# sel.net
KiCad netlist of a schematic drawn in EAGLE
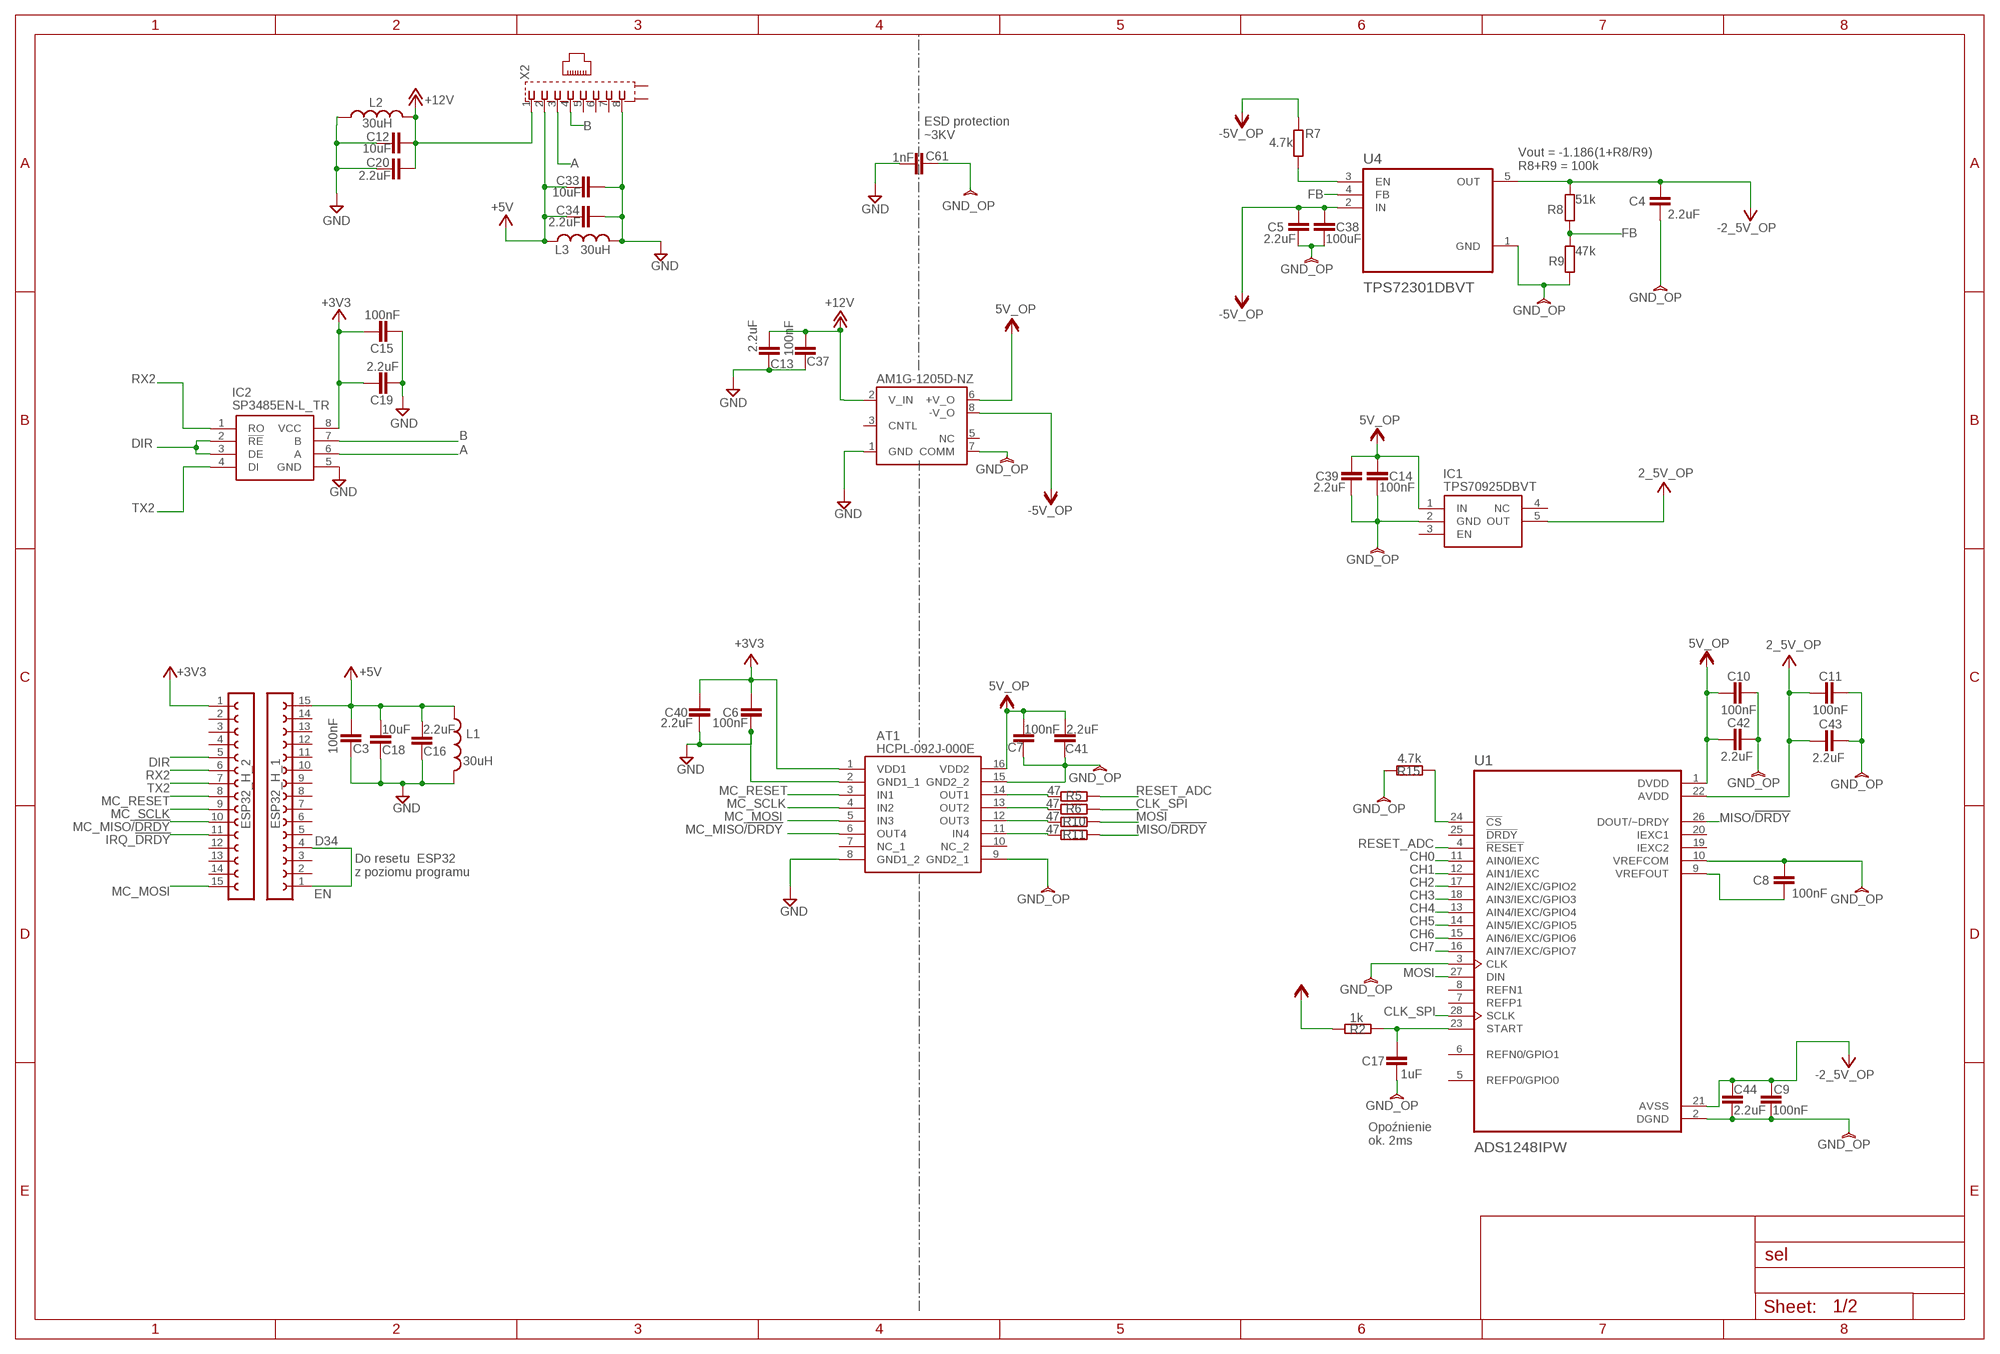
[diagram p0: schematic, sheet 1]
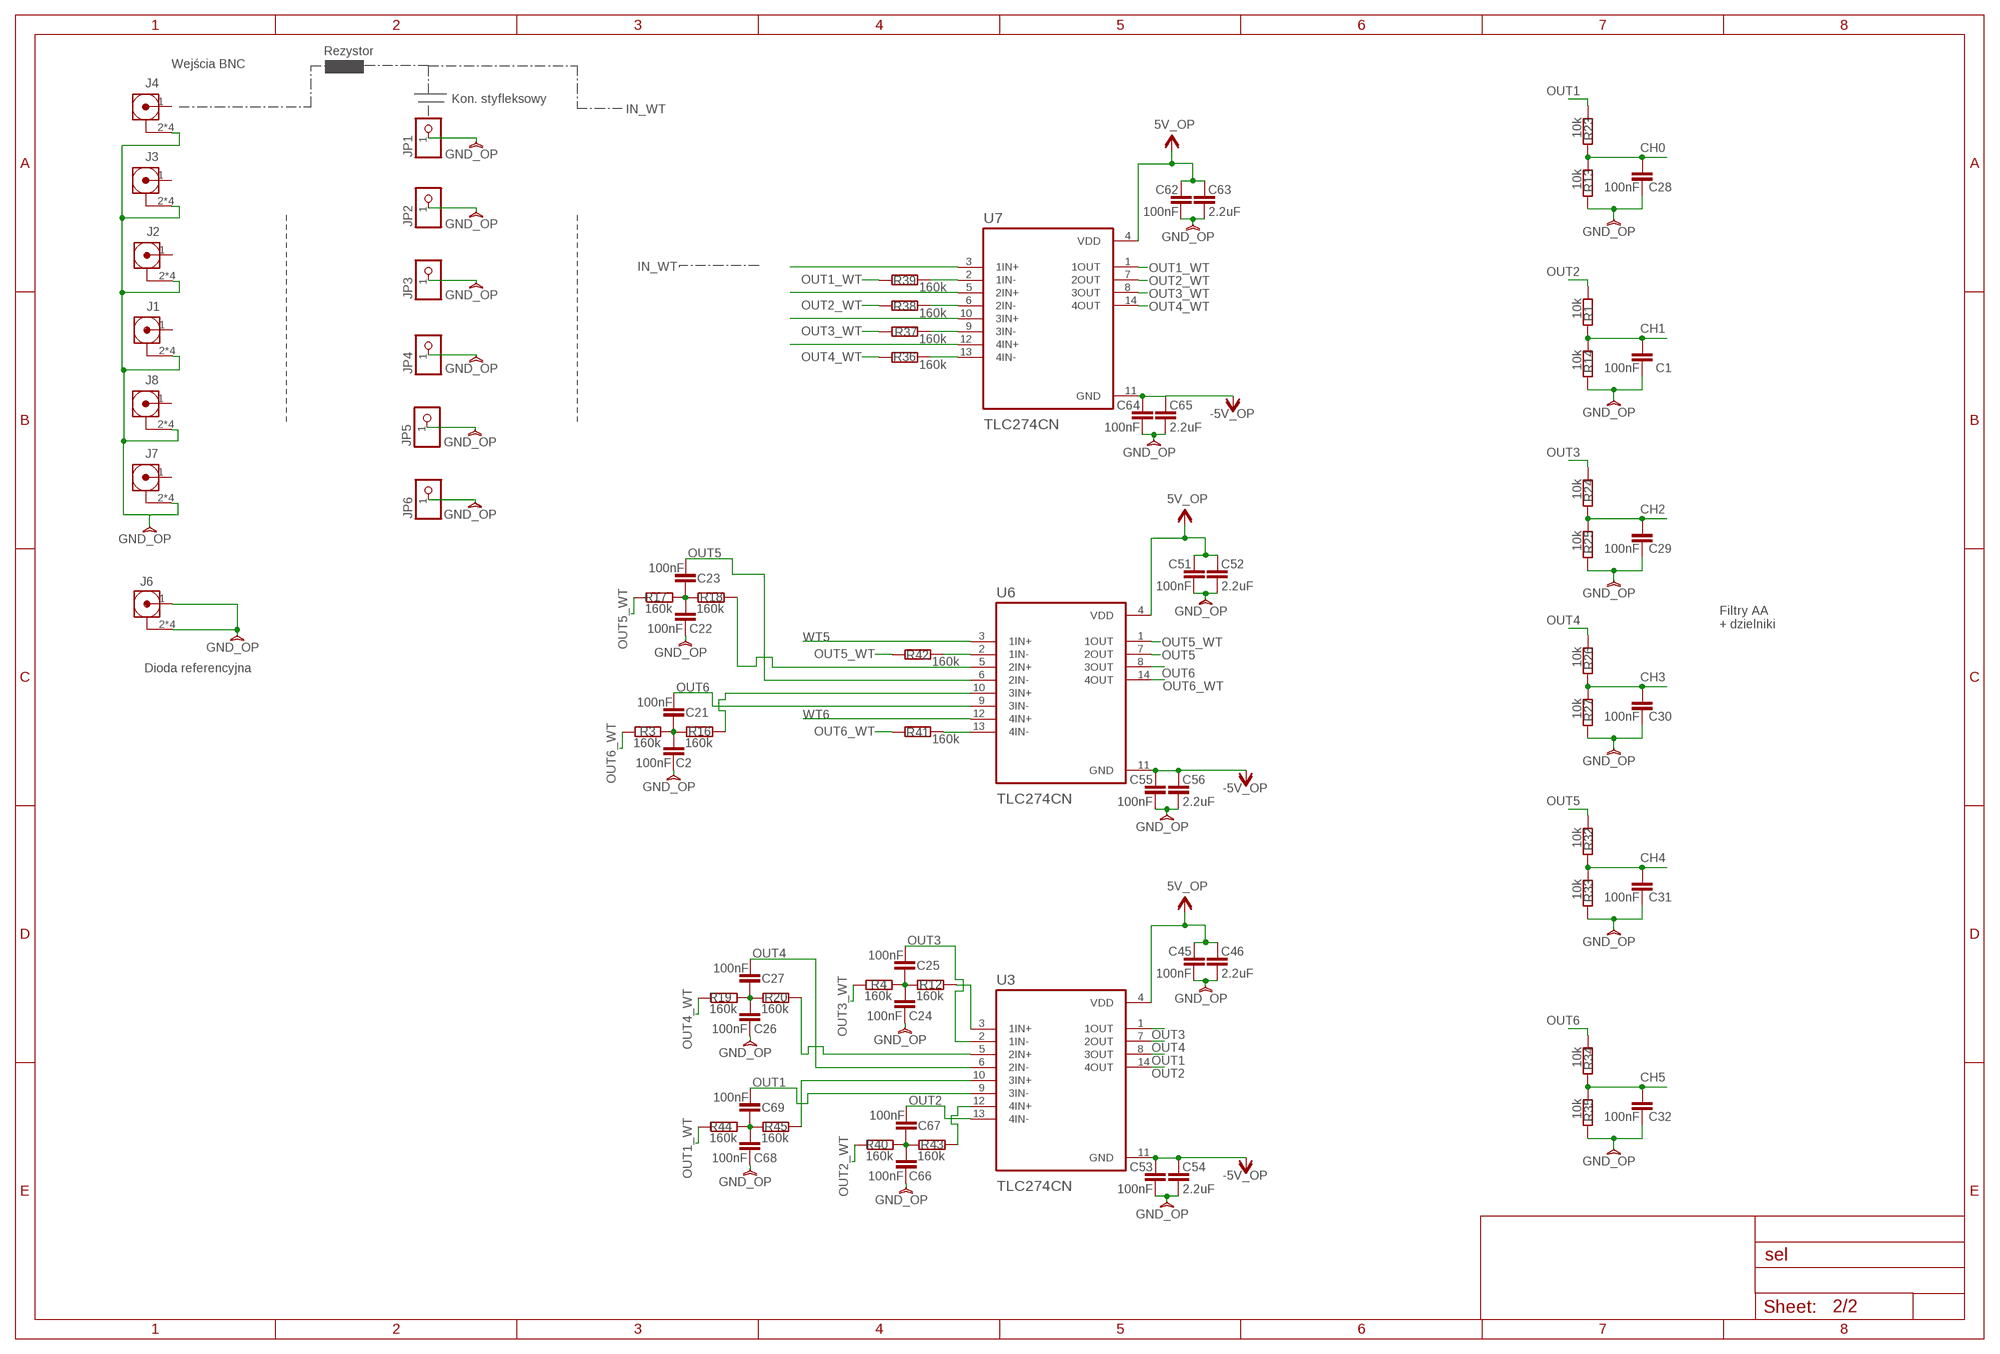
[diagram p1: schematic, sheet 2]

(export (version "E")
  (design (tool "Eeschema 10.0.6"))
  (components
    (comp (ref "AM1G-1205D-NZ")
      (value "AM1G-1205D-NZ")
      (footprint "eagle-import:AM1G-1205D-NZ")
      (libsource (lib "eagle-import") (part "AM1G-1205D-NZ"))
    )
    (comp (ref "AT1")
      (value "HCPL-092J-000E")
      (footprint "eagle-import:SOIC127P600X188-16N")
      (fields (field (name "MOUSER_PART_NUMBER") "630-HCPL-092J-000E"))
      (libsource (lib "eagle-import") (part "HCPL-092J-000E"))
    )
    (comp (ref "C3")
      (value "100nF")
      (footprint "eagle-import:C1206")
      (libsource (lib "eagle-import") (part "C-EUC1206"))
    )
    (comp (ref "C4")
      (value "2.2uF")
      (footprint "eagle-import:C1206")
      (libsource (lib "eagle-import") (part "C-EUC1206"))
    )
    (comp (ref "C5")
      (value "2.2uF")
      (footprint "eagle-import:C1206")
      (libsource (lib "eagle-import") (part "C-EUC1206"))
    )
    (comp (ref "C6")
      (value "100nF")
      (footprint "eagle-import:C1206")
      (libsource (lib "eagle-import") (part "C-EUC1206"))
    )
    (comp (ref "C7")
      (value "100nF")
      (footprint "eagle-import:C1206")
      (libsource (lib "eagle-import") (part "C-EUC1206"))
    )
    (comp (ref "C8")
      (value "100nF")
      (footprint "eagle-import:C1206")
      (libsource (lib "eagle-import") (part "C-EUC1206"))
    )
    (comp (ref "C9")
      (value "100nF")
      (footprint "eagle-import:C1206")
      (libsource (lib "eagle-import") (part "C-EUC1206"))
    )
    (comp (ref "C10")
      (value "100nF")
      (footprint "eagle-import:C1206")
      (libsource (lib "eagle-import") (part "C-EUC1206"))
    )
    (comp (ref "C11")
      (value "100nF")
      (footprint "eagle-import:C1206")
      (libsource (lib "eagle-import") (part "C-EUC1206"))
    )
    (comp (ref "C12")
      (value "10uF")
      (footprint "eagle-import:C1206")
      (libsource (lib "eagle-import") (part "C-EUC1206"))
    )
    (comp (ref "C13")
      (value "2.2uF")
      (footprint "eagle-import:C1206")
      (libsource (lib "eagle-import") (part "C-EUC1206"))
    )
    (comp (ref "C14")
      (value "100nF")
      (footprint "eagle-import:C1206")
      (libsource (lib "eagle-import") (part "C-EUC1206"))
    )
    (comp (ref "C15")
      (value "100nF")
      (footprint "eagle-import:C1206")
      (libsource (lib "eagle-import") (part "C-EUC1206"))
    )
    (comp (ref "C16")
      (value "2.2uF")
      (footprint "eagle-import:C1206")
      (libsource (lib "eagle-import") (part "C-EUC1206"))
    )
    (comp (ref "C17")
      (value "1uF")
      (footprint "eagle-import:C1206")
      (libsource (lib "eagle-import") (part "C-EUC1206"))
    )
    (comp (ref "C18")
      (value "10uF")
      (footprint "eagle-import:C1206")
      (libsource (lib "eagle-import") (part "C-EUC1206"))
    )
    (comp (ref "C19")
      (value "2.2uF")
      (footprint "eagle-import:C1206")
      (libsource (lib "eagle-import") (part "C-EUC1206"))
    )
    (comp (ref "C20")
      (value "2.2uF")
      (footprint "eagle-import:C1206")
      (libsource (lib "eagle-import") (part "C-EUC1206"))
    )
    (comp (ref "C33")
      (value "10uF")
      (footprint "eagle-import:C1206")
      (libsource (lib "eagle-import") (part "C-EUC1206"))
    )
    (comp (ref "C34")
      (value "2.2uF")
      (footprint "eagle-import:C1206")
      (libsource (lib "eagle-import") (part "C-EUC1206"))
    )
    (comp (ref "C37")
      (value "100nF")
      (footprint "eagle-import:C1206")
      (libsource (lib "eagle-import") (part "C-EUC1206"))
    )
    (comp (ref "C38")
      (value "100uF")
      (footprint "eagle-import:C1206")
      (libsource (lib "eagle-import") (part "C-EUC1206"))
    )
    (comp (ref "C39")
      (value "2.2uF")
      (footprint "eagle-import:C1206")
      (libsource (lib "eagle-import") (part "C-EUC1206"))
    )
    (comp (ref "C40")
      (value "2.2uF")
      (footprint "eagle-import:C1206")
      (libsource (lib "eagle-import") (part "C-EUC1206"))
    )
    (comp (ref "C41")
      (value "2.2uF")
      (footprint "eagle-import:C1206")
      (libsource (lib "eagle-import") (part "C-EUC1206"))
    )
    (comp (ref "C42")
      (value "2.2uF")
      (footprint "eagle-import:C1206")
      (libsource (lib "eagle-import") (part "C-EUC1206"))
    )
    (comp (ref "C43")
      (value "2.2uF")
      (footprint "eagle-import:C1206")
      (libsource (lib "eagle-import") (part "C-EUC1206"))
    )
    (comp (ref "C44")
      (value "2.2uF")
      (footprint "eagle-import:C1206")
      (libsource (lib "eagle-import") (part "C-EUC1206"))
    )
    (comp (ref "C61")
      (value "1nF")
      (footprint "eagle-import:C1206")
      (libsource (lib "eagle-import") (part "C-EUC1206"))
    )
    (comp (ref "ESP32_H_1")
      (value "FE15-1")
      (footprint "eagle-import:FE15")
      (libsource (lib "eagle-import") (part "FE15-1"))
    )
    (comp (ref "ESP32_H_2")
      (value "FE15-1")
      (footprint "eagle-import:FE15")
      (libsource (lib "eagle-import") (part "FE15-1"))
    )
    (comp (ref "IC1")
      (value "TPS70925DBVT")
      (footprint "eagle-import:SOT95P280X145-5N")
      (fields (field (name "MOUSER_PART_NUMBER") "595-TPS70925DBVT"))
      (libsource (lib "eagle-import") (part "TPS70925DBVT"))
    )
    (comp (ref "IC2")
      (value "SP3485EN-L_TR")
      (footprint "eagle-import:SOIC127P600X175-8N")
      (fields
        (field (name "MANUFACTURER_PART_NUMBER") "SP3485EN-L/TR")
        (field (name "MOUSER_PART_NUMBER") "701-SP3485EN-L/TR")
      )
      (libsource (lib "eagle-import") (part "SP3485EN-L_TR"))
    )
    (comp (ref "L1")
      (value "30uH")
      (footprint "eagle-import:0204_7")
      (libsource (lib "eagle-import") (part "L-US0204/7"))
    )
    (comp (ref "L2")
      (value "30uH")
      (footprint "eagle-import:0204_7")
      (libsource (lib "eagle-import") (part "L-US0204/7"))
    )
    (comp (ref "L3")
      (value "30uH")
      (footprint "eagle-import:0204_7")
      (libsource (lib "eagle-import") (part "L-US0204/7"))
    )
    (comp (ref "R2")
      (value "1k")
      (footprint "eagle-import:R1206")
      (libsource (lib "eagle-import") (part "R-EU_R1206"))
    )
    (comp (ref "R5")
      (value "47")
      (footprint "eagle-import:R1206")
      (libsource (lib "eagle-import") (part "R-EU_R1206"))
    )
    (comp (ref "R6")
      (value "47")
      (footprint "eagle-import:R1206")
      (libsource (lib "eagle-import") (part "R-EU_R1206"))
    )
    (comp (ref "R7")
      (value "4.7k")
      (footprint "eagle-import:R1206")
      (libsource (lib "eagle-import") (part "R-EU_R1206"))
    )
    (comp (ref "R8")
      (value "51k")
      (footprint "eagle-import:R1206")
      (libsource (lib "eagle-import") (part "R-EU_R1206"))
    )
    (comp (ref "R9")
      (value "47k")
      (footprint "eagle-import:R1206")
      (libsource (lib "eagle-import") (part "R-EU_R1206"))
    )
    (comp (ref "R10")
      (value "47")
      (footprint "eagle-import:R1206")
      (libsource (lib "eagle-import") (part "R-EU_R1206"))
    )
    (comp (ref "R11")
      (value "47")
      (footprint "eagle-import:R1206")
      (libsource (lib "eagle-import") (part "R-EU_R1206"))
    )
    (comp (ref "R15")
      (value "4.7k")
      (footprint "eagle-import:R1206")
      (libsource (lib "eagle-import") (part "R-EU_R1206"))
    )
    (comp (ref "U1")
      (value "ADS1248IPW")
      (footprint "eagle-import:SOP65P640X120-28N")
      (fields (field (name "MF") "Texas Instruments"))
      (libsource (lib "eagle-import") (part "ADS1248IPW"))
    )
    (comp (ref "U4")
      (value "TPS72301DBVT")
      (footprint "eagle-import:SOT95P280X145-5N")
      (fields (field (name "MF") "Texas Instruments"))
      (libsource (lib "eagle-import") (part "TPS72301DBVT"))
    )
    (comp (ref "X2")
      (value "0446200002")
      (footprint "eagle-import:0446200002")
      (fields (field (name "MF") "MOLEX"))
      (libsource (lib "eagle-import") (part "0446200002"))
    )
    (comp (ref "C1")
      (value "100nF")
      (footprint "eagle-import:C1206")
      (libsource (lib "eagle-import") (part "C-EUC1206"))
    )
    (comp (ref "C2")
      (value "100nF")
      (footprint "eagle-import:C1206")
      (libsource (lib "eagle-import") (part "C-EUC1206"))
    )
    (comp (ref "C21")
      (value "100nF")
      (footprint "eagle-import:C1206")
      (libsource (lib "eagle-import") (part "C-EUC1206"))
    )
    (comp (ref "C22")
      (value "100nF")
      (footprint "eagle-import:C1206")
      (libsource (lib "eagle-import") (part "C-EUC1206"))
    )
    (comp (ref "C23")
      (value "100nF")
      (footprint "eagle-import:C1206")
      (libsource (lib "eagle-import") (part "C-EUC1206"))
    )
    (comp (ref "C24")
      (value "100nF")
      (footprint "eagle-import:C1206")
      (libsource (lib "eagle-import") (part "C-EUC1206"))
    )
    (comp (ref "C25")
      (value "100nF")
      (footprint "eagle-import:C1206")
      (libsource (lib "eagle-import") (part "C-EUC1206"))
    )
    (comp (ref "C26")
      (value "100nF")
      (footprint "eagle-import:C1206")
      (libsource (lib "eagle-import") (part "C-EUC1206"))
    )
    (comp (ref "C27")
      (value "100nF")
      (footprint "eagle-import:C1206")
      (libsource (lib "eagle-import") (part "C-EUC1206"))
    )
    (comp (ref "C28")
      (value "100nF")
      (footprint "eagle-import:C1206")
      (libsource (lib "eagle-import") (part "C-EUC1206"))
    )
    (comp (ref "C29")
      (value "100nF")
      (footprint "eagle-import:C1206")
      (libsource (lib "eagle-import") (part "C-EUC1206"))
    )
    (comp (ref "C30")
      (value "100nF")
      (footprint "eagle-import:C1206")
      (libsource (lib "eagle-import") (part "C-EUC1206"))
    )
    (comp (ref "C31")
      (value "100nF")
      (footprint "eagle-import:C1206")
      (libsource (lib "eagle-import") (part "C-EUC1206"))
    )
    (comp (ref "C32")
      (value "100nF")
      (footprint "eagle-import:C1206")
      (libsource (lib "eagle-import") (part "C-EUC1206"))
    )
    (comp (ref "C45")
      (value "100nF")
      (footprint "eagle-import:C1206")
      (libsource (lib "eagle-import") (part "C-EUC1206"))
    )
    (comp (ref "C46")
      (value "2.2uF")
      (footprint "eagle-import:C1206")
      (libsource (lib "eagle-import") (part "C-EUC1206"))
    )
    (comp (ref "C51")
      (value "100nF")
      (footprint "eagle-import:C1206")
      (libsource (lib "eagle-import") (part "C-EUC1206"))
    )
    (comp (ref "C52")
      (value "2.2uF")
      (footprint "eagle-import:C1206")
      (libsource (lib "eagle-import") (part "C-EUC1206"))
    )
    (comp (ref "C53")
      (value "100nF")
      (footprint "eagle-import:C1206")
      (libsource (lib "eagle-import") (part "C-EUC1206"))
    )
    (comp (ref "C54")
      (value "2.2uF")
      (footprint "eagle-import:C1206")
      (libsource (lib "eagle-import") (part "C-EUC1206"))
    )
    (comp (ref "C55")
      (value "100nF")
      (footprint "eagle-import:C1206")
      (libsource (lib "eagle-import") (part "C-EUC1206"))
    )
    (comp (ref "C56")
      (value "2.2uF")
      (footprint "eagle-import:C1206")
      (libsource (lib "eagle-import") (part "C-EUC1206"))
    )
    (comp (ref "C62")
      (value "100nF")
      (footprint "eagle-import:C1206")
      (libsource (lib "eagle-import") (part "C-EUC1206"))
    )
    (comp (ref "C63")
      (value "2.2uF")
      (footprint "eagle-import:C1206")
      (libsource (lib "eagle-import") (part "C-EUC1206"))
    )
    (comp (ref "C64")
      (value "100nF")
      (footprint "eagle-import:C1206")
      (libsource (lib "eagle-import") (part "C-EUC1206"))
    )
    (comp (ref "C65")
      (value "2.2uF")
      (footprint "eagle-import:C1206")
      (libsource (lib "eagle-import") (part "C-EUC1206"))
    )
    (comp (ref "C66")
      (value "100nF")
      (footprint "eagle-import:C1206")
      (libsource (lib "eagle-import") (part "C-EUC1206"))
    )
    (comp (ref "C67")
      (value "100nF")
      (footprint "eagle-import:C1206")
      (libsource (lib "eagle-import") (part "C-EUC1206"))
    )
    (comp (ref "C68")
      (value "100nF")
      (footprint "eagle-import:C1206")
      (libsource (lib "eagle-import") (part "C-EUC1206"))
    )
    (comp (ref "C69")
      (value "100nF")
      (footprint "eagle-import:C1206")
      (libsource (lib "eagle-import") (part "C-EUC1206"))
    )
    (comp (ref "J1")
      (value "5-1634556-0")
      (footprint "eagle-import:TE_5-1634556-0")
      (fields (field (name "MF") "TE Connectivity"))
      (libsource (lib "eagle-import") (part "5-1634556-0"))
    )
    (comp (ref "J2")
      (value "5-1634556-0")
      (footprint "eagle-import:TE_5-1634556-0")
      (fields (field (name "MF") "TE Connectivity"))
      (libsource (lib "eagle-import") (part "5-1634556-0"))
    )
    (comp (ref "J3")
      (value "5-1634556-0")
      (footprint "eagle-import:TE_5-1634556-0")
      (fields (field (name "MF") "TE Connectivity"))
      (libsource (lib "eagle-import") (part "5-1634556-0"))
    )
    (comp (ref "J4")
      (value "5-1634556-0")
      (footprint "eagle-import:TE_5-1634556-0")
      (fields (field (name "MF") "TE Connectivity"))
      (libsource (lib "eagle-import") (part "5-1634556-0"))
    )
    (comp (ref "J6")
      (value "5-1634556-0")
      (footprint "eagle-import:TE_5-1634556-0")
      (fields (field (name "MF") "TE Connectivity"))
      (libsource (lib "eagle-import") (part "5-1634556-0"))
    )
    (comp (ref "J7")
      (value "5-1634556-0")
      (footprint "eagle-import:TE_5-1634556-0")
      (fields (field (name "MF") "TE Connectivity"))
      (libsource (lib "eagle-import") (part "5-1634556-0"))
    )
    (comp (ref "J8")
      (value "5-1634556-0")
      (footprint "eagle-import:TE_5-1634556-0")
      (fields (field (name "MF") "TE Connectivity"))
      (libsource (lib "eagle-import") (part "5-1634556-0"))
    )
    (comp (ref "JP1")
      (value "PINHD-1X1")
      (footprint "eagle-import:1X01")
      (libsource (lib "eagle-import") (part "PINHD-1X1"))
    )
    (comp (ref "JP2")
      (value "PINHD-1X1")
      (footprint "eagle-import:1X01")
      (libsource (lib "eagle-import") (part "PINHD-1X1"))
    )
    (comp (ref "JP3")
      (value "PINHD-1X1")
      (footprint "eagle-import:1X01")
      (libsource (lib "eagle-import") (part "PINHD-1X1"))
    )
    (comp (ref "JP4")
      (value "PINHD-1X1")
      (footprint "eagle-import:1X01")
      (libsource (lib "eagle-import") (part "PINHD-1X1"))
    )
    (comp (ref "JP5")
      (value "PINHD-1X1")
      (footprint "eagle-import:1X01")
      (libsource (lib "eagle-import") (part "PINHD-1X1"))
    )
    (comp (ref "JP6")
      (value "PINHD-1X1")
      (footprint "eagle-import:1X01")
      (libsource (lib "eagle-import") (part "PINHD-1X1"))
    )
    (comp (ref "R1")
      (value "10k")
      (footprint "eagle-import:R1206")
      (libsource (lib "eagle-import") (part "R-EU_R1206"))
    )
    (comp (ref "R3")
      (value "160k")
      (footprint "eagle-import:R1206")
      (libsource (lib "eagle-import") (part "R-EU_R1206"))
    )
    (comp (ref "R4")
      (value "160k")
      (footprint "eagle-import:R1206")
      (libsource (lib "eagle-import") (part "R-EU_R1206"))
    )
    (comp (ref "R12")
      (value "160k")
      (footprint "eagle-import:R1206")
      (libsource (lib "eagle-import") (part "R-EU_R1206"))
    )
    (comp (ref "R13")
      (value "10k")
      (footprint "eagle-import:R1206")
      (libsource (lib "eagle-import") (part "R-EU_R1206"))
    )
    (comp (ref "R14")
      (value "10k")
      (footprint "eagle-import:R1206")
      (libsource (lib "eagle-import") (part "R-EU_R1206"))
    )
    (comp (ref "R16")
      (value "160k")
      (footprint "eagle-import:R1206")
      (libsource (lib "eagle-import") (part "R-EU_R1206"))
    )
    (comp (ref "R17")
      (value "160k")
      (footprint "eagle-import:R1206")
      (libsource (lib "eagle-import") (part "R-EU_R1206"))
    )
    (comp (ref "R18")
      (value "160k")
      (footprint "eagle-import:R1206")
      (libsource (lib "eagle-import") (part "R-EU_R1206"))
    )
    (comp (ref "R19")
      (value "160k")
      (footprint "eagle-import:R1206")
      (libsource (lib "eagle-import") (part "R-EU_R1206"))
    )
    (comp (ref "R20")
      (value "160k")
      (footprint "eagle-import:R1206")
      (libsource (lib "eagle-import") (part "R-EU_R1206"))
    )
    (comp (ref "R23")
      (value "10k")
      (footprint "eagle-import:R1206")
      (libsource (lib "eagle-import") (part "R-EU_R1206"))
    )
    (comp (ref "R24")
      (value "10k")
      (footprint "eagle-import:R1206")
      (libsource (lib "eagle-import") (part "R-EU_R1206"))
    )
    (comp (ref "R25")
      (value "10k")
      (footprint "eagle-import:R1206")
      (libsource (lib "eagle-import") (part "R-EU_R1206"))
    )
    (comp (ref "R26")
      (value "10k")
      (footprint "eagle-import:R1206")
      (libsource (lib "eagle-import") (part "R-EU_R1206"))
    )
    (comp (ref "R27")
      (value "10k")
      (footprint "eagle-import:R1206")
      (libsource (lib "eagle-import") (part "R-EU_R1206"))
    )
    (comp (ref "R32")
      (value "10k")
      (footprint "eagle-import:R1206")
      (libsource (lib "eagle-import") (part "R-EU_R1206"))
    )
    (comp (ref "R33")
      (value "10k")
      (footprint "eagle-import:R1206")
      (libsource (lib "eagle-import") (part "R-EU_R1206"))
    )
    (comp (ref "R34")
      (value "10k")
      (footprint "eagle-import:R1206")
      (libsource (lib "eagle-import") (part "R-EU_R1206"))
    )
    (comp (ref "R35")
      (value "10k")
      (footprint "eagle-import:R1206")
      (libsource (lib "eagle-import") (part "R-EU_R1206"))
    )
    (comp (ref "R36")
      (value "160k")
      (footprint "eagle-import:R1206")
      (libsource (lib "eagle-import") (part "R-EU_R1206"))
    )
    (comp (ref "R37")
      (value "160k")
      (footprint "eagle-import:R1206")
      (libsource (lib "eagle-import") (part "R-EU_R1206"))
    )
    (comp (ref "R38")
      (value "160k")
      (footprint "eagle-import:R1206")
      (libsource (lib "eagle-import") (part "R-EU_R1206"))
    )
    (comp (ref "R39")
      (value "160k")
      (footprint "eagle-import:R1206")
      (libsource (lib "eagle-import") (part "R-EU_R1206"))
    )
    (comp (ref "R40")
      (value "160k")
      (footprint "eagle-import:R1206")
      (libsource (lib "eagle-import") (part "R-EU_R1206"))
    )
    (comp (ref "R41")
      (value "160k")
      (footprint "eagle-import:R1206")
      (libsource (lib "eagle-import") (part "R-EU_R1206"))
    )
    (comp (ref "R42")
      (value "160k")
      (footprint "eagle-import:R1206")
      (libsource (lib "eagle-import") (part "R-EU_R1206"))
    )
    (comp (ref "R43")
      (value "160k")
      (footprint "eagle-import:R1206")
      (libsource (lib "eagle-import") (part "R-EU_R1206"))
    )
    (comp (ref "R44")
      (value "160k")
      (footprint "eagle-import:R1206")
      (libsource (lib "eagle-import") (part "R-EU_R1206"))
    )
    (comp (ref "R45")
      (value "160k")
      (footprint "eagle-import:R1206")
      (libsource (lib "eagle-import") (part "R-EU_R1206"))
    )
    (comp (ref "U3")
      (value "TLC274CN")
      (footprint "eagle-import:DIP794W45P254L1969H508Q14")
      (fields (field (name "MF") "Texas Instruments"))
      (libsource (lib "eagle-import") (part "TLC274CN"))
    )
    (comp (ref "U6")
      (value "TLC274CN")
      (footprint "eagle-import:DIP794W45P254L1969H508Q14")
      (fields (field (name "MF") "Texas Instruments"))
      (libsource (lib "eagle-import") (part "TLC274CN"))
    )
    (comp (ref "U7")
      (value "TLC274CN")
      (footprint "eagle-import:DIP794W45P254L1969H508Q14")
      (fields (field (name "MF") "Texas Instruments"))
      (libsource (lib "eagle-import") (part "TLC274CN"))
    )
  )
  (nets
    (net (code "1") (name "+3V3") (class "Default")
      (node (ref "AT1") (pin "1") (pinfunction "VDD1_1") (pintype "bidirectional"))
      (node (ref "C15") (pin "2") (pinfunction "2_2") (pintype "passive"))
      (node (ref "C19") (pin "2") (pinfunction "2_2") (pintype "passive"))
      (node (ref "C40") (pin "2") (pinfunction "2_2") (pintype "passive"))
      (node (ref "C6") (pin "2") (pinfunction "2_2") (pintype "passive"))
      (node (ref "ESP32_H_2") (pin "1") (pinfunction "1_1") (pintype "passive"))
      (node (ref "IC2") (pin "8") (pinfunction "VCC_8") (pintype "bidirectional"))
    )
    (net (code "2") (name "+5V") (class "Default")
      (node (ref "C16") (pin "1") (pinfunction "1_1") (pintype "passive"))
      (node (ref "C18") (pin "1") (pinfunction "1_1") (pintype "passive"))
      (node (ref "C3") (pin "1") (pinfunction "1_1") (pintype "passive"))
      (node (ref "C33") (pin "2") (pinfunction "2_2") (pintype "passive"))
      (node (ref "C34") (pin "2") (pinfunction "2_2") (pintype "passive"))
      (node (ref "ESP32_H_1") (pin "15") (pinfunction "15_15") (pintype "passive"))
      (node (ref "L1") (pin "1") (pinfunction "1_1") (pintype "passive"))
      (node (ref "L3") (pin "1") (pinfunction "1_1") (pintype "passive"))
      (node (ref "X2") (pin "2") (pinfunction "2_2") (pintype "passive"))
    )
    (net (code "3") (name "+12V") (class "Default")
      (node (ref "AM1G-1205D-NZ") (pin "2") (pinfunction "V_IN_2") (pintype "bidirectional"))
      (node (ref "C12") (pin "1") (pinfunction "1_1") (pintype "passive"))
      (node (ref "C13") (pin "2") (pinfunction "2_2") (pintype "passive"))
      (node (ref "C20") (pin "1") (pinfunction "1_1") (pintype "passive"))
      (node (ref "C37") (pin "2") (pinfunction "2_2") (pintype "passive"))
      (node (ref "L2") (pin "2") (pinfunction "2_2") (pintype "passive"))
      (node (ref "X2") (pin "1") (pinfunction "1_1") (pintype "passive"))
    )
    (net (code "4") (name "-2_5V_OP") (class "Default")
      (node (ref "C4") (pin "1") (pinfunction "1_1") (pintype "passive"))
      (node (ref "C44") (pin "1") (pinfunction "1_1") (pintype "passive"))
      (node (ref "C9") (pin "1") (pinfunction "1_1") (pintype "passive"))
      (node (ref "R8") (pin "2") (pinfunction "2_2") (pintype "passive"))
      (node (ref "U1") (pin "21") (pinfunction "AVSS_21") (pintype "power_in"))
      (node (ref "U4") (pin "5") (pinfunction "OUT_5") (pintype "output"))
    )
    (net (code "5") (name "-5V_OP") (class "Default")
      (node (ref "AM1G-1205D-NZ") (pin "8") (pinfunction "-V_O_8") (pintype "bidirectional"))
      (node (ref "C38") (pin "1") (pinfunction "1_1") (pintype "passive"))
      (node (ref "C5") (pin "1") (pinfunction "1_1") (pintype "passive"))
      (node (ref "C53") (pin "2") (pinfunction "2_2") (pintype "passive"))
      (node (ref "C54") (pin "2") (pinfunction "2_2") (pintype "passive"))
      (node (ref "C55") (pin "2") (pinfunction "2_2") (pintype "passive"))
      (node (ref "C56") (pin "2") (pinfunction "2_2") (pintype "passive"))
      (node (ref "C64") (pin "2") (pinfunction "2_2") (pintype "passive"))
      (node (ref "C65") (pin "2") (pinfunction "2_2") (pintype "passive"))
      (node (ref "R7") (pin "1") (pinfunction "1_1") (pintype "passive"))
      (node (ref "U3") (pin "11") (pinfunction "GND_11") (pintype "power_in"))
      (node (ref "U4") (pin "2") (pinfunction "IN_2") (pintype "input"))
      (node (ref "U6") (pin "11") (pinfunction "GND_11") (pintype "power_in"))
      (node (ref "U7") (pin "11") (pinfunction "GND_11") (pintype "power_in"))
    )
    (net (code "6") (name "2_5V_OP") (class "Default")
      (node (ref "C11") (pin "2") (pinfunction "2_2") (pintype "passive"))
      (node (ref "C43") (pin "2") (pinfunction "2_2") (pintype "passive"))
      (node (ref "IC1") (pin "5") (pinfunction "OUT_5") (pintype "bidirectional"))
      (node (ref "U1") (pin "22") (pinfunction "AVDD_22") (pintype "power_in"))
    )
    (net (code "7") (name "5V_OP") (class "Default")
      (node (ref "AM1G-1205D-NZ") (pin "6") (pinfunction "+V_O_6") (pintype "bidirectional"))
      (node (ref "AT1") (pin "16") (pinfunction "VDD2_16") (pintype "bidirectional"))
      (node (ref "C10") (pin "2") (pinfunction "2_2") (pintype "passive"))
      (node (ref "C14") (pin "1") (pinfunction "1_1") (pintype "passive"))
      (node (ref "C39") (pin "1") (pinfunction "1_1") (pintype "passive"))
      (node (ref "C41") (pin "1") (pinfunction "1_1") (pintype "passive"))
      (node (ref "C42") (pin "2") (pinfunction "2_2") (pintype "passive"))
      (node (ref "C45") (pin "2") (pinfunction "2_2") (pintype "passive"))
      (node (ref "C46") (pin "2") (pinfunction "2_2") (pintype "passive"))
      (node (ref "C51") (pin "2") (pinfunction "2_2") (pintype "passive"))
      (node (ref "C52") (pin "2") (pinfunction "2_2") (pintype "passive"))
      (node (ref "C62") (pin "2") (pinfunction "2_2") (pintype "passive"))
      (node (ref "C63") (pin "2") (pinfunction "2_2") (pintype "passive"))
      (node (ref "C7") (pin "1") (pinfunction "1_1") (pintype "passive"))
      (node (ref "IC1") (pin "1") (pinfunction "IN_1") (pintype "bidirectional"))
      (node (ref "R2") (pin "2") (pinfunction "2_2") (pintype "passive"))
      (node (ref "U1") (pin "1") (pinfunction "DVDD_1") (pintype "power_in"))
      (node (ref "U3") (pin "4") (pinfunction "VDD_4") (pintype "power_in"))
      (node (ref "U6") (pin "4") (pinfunction "VDD_4") (pintype "power_in"))
      (node (ref "U7") (pin "4") (pinfunction "VDD_4") (pintype "power_in"))
    )
    (net (code "8") (name "A") (class "Default")
      (node (ref "IC2") (pin "6") (pinfunction "A_6") (pintype "bidirectional"))
      (node (ref "X2") (pin "3") (pinfunction "3_3") (pintype "passive"))
    )
    (net (code "9") (name "B") (class "Default")
      (node (ref "IC2") (pin "7") (pinfunction "B_7") (pintype "bidirectional"))
      (node (ref "X2") (pin "4") (pinfunction "4_4") (pintype "passive"))
    )
    (net (code "10") (name "CH0") (class "Default")
      (node (ref "C28") (pin "1") (pinfunction "1_1") (pintype "passive"))
      (node (ref "R13") (pin "2") (pinfunction "2_2") (pintype "passive"))
      (node (ref "R23") (pin "1") (pinfunction "1_1") (pintype "passive"))
      (node (ref "U1") (pin "11") (pinfunction "AIN0/IEXC_11") (pintype "input"))
    )
    (net (code "11") (name "CH1") (class "Default")
      (node (ref "C1") (pin "1") (pinfunction "1_1") (pintype "passive"))
      (node (ref "R1") (pin "1") (pinfunction "1_1") (pintype "passive"))
      (node (ref "R14") (pin "2") (pinfunction "2_2") (pintype "passive"))
      (node (ref "U1") (pin "12") (pinfunction "AIN1/IEXC_12") (pintype "input"))
    )
    (net (code "12") (name "CH2") (class "Default")
      (node (ref "C29") (pin "1") (pinfunction "1_1") (pintype "passive"))
      (node (ref "R24") (pin "1") (pinfunction "1_1") (pintype "passive"))
      (node (ref "R25") (pin "2") (pinfunction "2_2") (pintype "passive"))
      (node (ref "U1") (pin "17") (pinfunction "AIN2/IEXC/GPIO2_17") (pintype "input"))
    )
    (net (code "13") (name "CH3") (class "Default")
      (node (ref "C30") (pin "1") (pinfunction "1_1") (pintype "passive"))
      (node (ref "R26") (pin "1") (pinfunction "1_1") (pintype "passive"))
      (node (ref "R27") (pin "2") (pinfunction "2_2") (pintype "passive"))
      (node (ref "U1") (pin "18") (pinfunction "AIN3/IEXC/GPIO3_18") (pintype "input"))
    )
    (net (code "14") (name "CH4") (class "Default")
      (node (ref "C31") (pin "1") (pinfunction "1_1") (pintype "passive"))
      (node (ref "R32") (pin "1") (pinfunction "1_1") (pintype "passive"))
      (node (ref "R33") (pin "2") (pinfunction "2_2") (pintype "passive"))
      (node (ref "U1") (pin "13") (pinfunction "AIN4/IEXC/GPIO4_13") (pintype "input"))
    )
    (net (code "15") (name "CH5") (class "Default")
      (node (ref "C32") (pin "1") (pinfunction "1_1") (pintype "passive"))
      (node (ref "R34") (pin "1") (pinfunction "1_1") (pintype "passive"))
      (node (ref "R35") (pin "2") (pinfunction "2_2") (pintype "passive"))
      (node (ref "U1") (pin "14") (pinfunction "AIN5/IEXC/GPIO5_14") (pintype "input"))
    )
    (net (code "16") (name "CH6") (class "Default")
      (node (ref "U1") (pin "15") (pinfunction "AIN6/IEXC/GPIO6_15") (pintype "input"))
    )
    (net (code "17") (name "CH7") (class "Default")
      (node (ref "U1") (pin "16") (pinfunction "AIN7/IEXC/GPIO7_16") (pintype "input"))
    )
    (net (code "18") (name "CLK_SPI") (class "Default")
      (node (ref "AT1") (pin "13") (pinfunction "OUT2_13") (pintype "bidirectional"))
      (node (ref "R6") (pin "2") (pinfunction "2_2") (pintype "passive"))
      (node (ref "U1") (pin "28") (pinfunction "SCLK_28") (pintype "input"))
    )
    (net (code "19") (name "DIR") (class "Default")
      (node (ref "ESP32_H_2") (pin "5") (pinfunction "5_5") (pintype "passive"))
      (node (ref "IC2") (pin "2") (pinfunction "~{RE}_2") (pintype "bidirectional"))
      (node (ref "IC2") (pin "3") (pinfunction "DE_3") (pintype "bidirectional"))
    )
    (net (code "20") (name "EN") (class "Default")
      (node (ref "ESP32_H_1") (pin "1") (pinfunction "1_1") (pintype "passive"))
      (node (ref "ESP32_H_1") (pin "4") (pinfunction "4_4") (pintype "passive"))
    )
    (net (code "21") (name "FB") (class "Default")
      (node (ref "R8") (pin "1") (pinfunction "1_1") (pintype "passive"))
      (node (ref "R9") (pin "2") (pinfunction "2_2") (pintype "passive"))
      (node (ref "U4") (pin "4") (pinfunction "FB_4") (pintype "input"))
    )
    (net (code "22") (name "GND") (class "Default")
      (node (ref "AM1G-1205D-NZ") (pin "1") (pinfunction "GND_1") (pintype "bidirectional"))
      (node (ref "AT1") (pin "2") (pinfunction "GND1_1_2") (pintype "bidirectional"))
      (node (ref "AT1") (pin "8") (pinfunction "GND1_2_8") (pintype "bidirectional"))
      (node (ref "C12") (pin "2") (pinfunction "2_2") (pintype "passive"))
      (node (ref "C13") (pin "1") (pinfunction "1_1") (pintype "passive"))
      (node (ref "C15") (pin "1") (pinfunction "1_1") (pintype "passive"))
      (node (ref "C16") (pin "2") (pinfunction "2_2") (pintype "passive"))
      (node (ref "C18") (pin "2") (pinfunction "2_2") (pintype "passive"))
      (node (ref "C19") (pin "1") (pinfunction "1_1") (pintype "passive"))
      (node (ref "C20") (pin "2") (pinfunction "2_2") (pintype "passive"))
      (node (ref "C3") (pin "2") (pinfunction "2_2") (pintype "passive"))
      (node (ref "C33") (pin "1") (pinfunction "1_1") (pintype "passive"))
      (node (ref "C34") (pin "1") (pinfunction "1_1") (pintype "passive"))
      (node (ref "C37") (pin "1") (pinfunction "1_1") (pintype "passive"))
      (node (ref "C40") (pin "1") (pinfunction "1_1") (pintype "passive"))
      (node (ref "C6") (pin "1") (pinfunction "1_1") (pintype "passive"))
      (node (ref "C61") (pin "2") (pinfunction "2_2") (pintype "passive"))
      (node (ref "IC2") (pin "5") (pinfunction "GND_5") (pintype "bidirectional"))
      (node (ref "L1") (pin "2") (pinfunction "2_2") (pintype "passive"))
      (node (ref "L2") (pin "1") (pinfunction "1_1") (pintype "passive"))
      (node (ref "L3") (pin "2") (pinfunction "2_2") (pintype "passive"))
      (node (ref "X2") (pin "8") (pinfunction "8_8") (pintype "passive"))
    )
    (net (code "23") (name "GND_OP") (class "Default")
      (node (ref "AM1G-1205D-NZ") (pin "7") (pinfunction "COMM_7") (pintype "bidirectional"))
      (node (ref "AT1") (pin "15") (pinfunction "GND2_2_15") (pintype "bidirectional"))
      (node (ref "AT1") (pin "9") (pinfunction "GND2_1_9") (pintype "bidirectional"))
      (node (ref "C1") (pin "2") (pinfunction "2_2") (pintype "passive"))
      (node (ref "C10") (pin "1") (pinfunction "1_1") (pintype "passive"))
      (node (ref "C11") (pin "1") (pinfunction "1_1") (pintype "passive"))
      (node (ref "C14") (pin "2") (pinfunction "2_2") (pintype "passive"))
      (node (ref "C17") (pin "2") (pinfunction "2_2") (pintype "passive"))
      (node (ref "C2") (pin "2") (pinfunction "2_2") (pintype "passive"))
      (node (ref "C22") (pin "2") (pinfunction "2_2") (pintype "passive"))
      (node (ref "C24") (pin "2") (pinfunction "2_2") (pintype "passive"))
      (node (ref "C26") (pin "2") (pinfunction "2_2") (pintype "passive"))
      (node (ref "C28") (pin "2") (pinfunction "2_2") (pintype "passive"))
      (node (ref "C29") (pin "2") (pinfunction "2_2") (pintype "passive"))
      (node (ref "C30") (pin "2") (pinfunction "2_2") (pintype "passive"))
      (node (ref "C31") (pin "2") (pinfunction "2_2") (pintype "passive"))
      (node (ref "C32") (pin "2") (pinfunction "2_2") (pintype "passive"))
      (node (ref "C38") (pin "2") (pinfunction "2_2") (pintype "passive"))
      (node (ref "C39") (pin "2") (pinfunction "2_2") (pintype "passive"))
      (node (ref "C4") (pin "2") (pinfunction "2_2") (pintype "passive"))
      (node (ref "C41") (pin "2") (pinfunction "2_2") (pintype "passive"))
      (node (ref "C42") (pin "1") (pinfunction "1_1") (pintype "passive"))
      (node (ref "C43") (pin "1") (pinfunction "1_1") (pintype "passive"))
      (node (ref "C44") (pin "2") (pinfunction "2_2") (pintype "passive"))
      (node (ref "C45") (pin "1") (pinfunction "1_1") (pintype "passive"))
      (node (ref "C46") (pin "1") (pinfunction "1_1") (pintype "passive"))
      (node (ref "C5") (pin "2") (pinfunction "2_2") (pintype "passive"))
      (node (ref "C51") (pin "1") (pinfunction "1_1") (pintype "passive"))
      (node (ref "C52") (pin "1") (pinfunction "1_1") (pintype "passive"))
      (node (ref "C53") (pin "1") (pinfunction "1_1") (pintype "passive"))
      (node (ref "C54") (pin "1") (pinfunction "1_1") (pintype "passive"))
      (node (ref "C55") (pin "1") (pinfunction "1_1") (pintype "passive"))
      (node (ref "C56") (pin "1") (pinfunction "1_1") (pintype "passive"))
      (node (ref "C61") (pin "1") (pinfunction "1_1") (pintype "passive"))
      (node (ref "C62") (pin "1") (pinfunction "1_1") (pintype "passive"))
      (node (ref "C63") (pin "1") (pinfunction "1_1") (pintype "passive"))
      (node (ref "C64") (pin "1") (pinfunction "1_1") (pintype "passive"))
      (node (ref "C65") (pin "1") (pinfunction "1_1") (pintype "passive"))
      (node (ref "C66") (pin "2") (pinfunction "2_2") (pintype "passive"))
      (node (ref "C68") (pin "2") (pinfunction "2_2") (pintype "passive"))
      (node (ref "C7") (pin "2") (pinfunction "2_2") (pintype "passive"))
      (node (ref "C8") (pin "1") (pinfunction "1_1") (pintype "passive"))
      (node (ref "C9") (pin "2") (pinfunction "2_2") (pintype "passive"))
      (node (ref "IC1") (pin "2") (pinfunction "GND_2") (pintype "bidirectional"))
      (node (ref "J1") (pin "2") (pinfunction "2_2") (pintype "passive"))
      (node (ref "J1") (pin "3") (pinfunction "2_3") (pintype "passive"))
      (node (ref "J1") (pin "4") (pinfunction "2_4") (pintype "passive"))
      (node (ref "J1") (pin "5") (pinfunction "2_5") (pintype "passive"))
      (node (ref "J2") (pin "2") (pinfunction "2_2") (pintype "passive"))
      (node (ref "J2") (pin "3") (pinfunction "2_3") (pintype "passive"))
      (node (ref "J2") (pin "4") (pinfunction "2_4") (pintype "passive"))
      (node (ref "J2") (pin "5") (pinfunction "2_5") (pintype "passive"))
      (node (ref "J3") (pin "2") (pinfunction "2_2") (pintype "passive"))
      (node (ref "J3") (pin "3") (pinfunction "2_3") (pintype "passive"))
      (node (ref "J3") (pin "4") (pinfunction "2_4") (pintype "passive"))
      (node (ref "J3") (pin "5") (pinfunction "2_5") (pintype "passive"))
      (node (ref "J4") (pin "2") (pinfunction "2_2") (pintype "passive"))
      (node (ref "J4") (pin "3") (pinfunction "2_3") (pintype "passive"))
      (node (ref "J4") (pin "4") (pinfunction "2_4") (pintype "passive"))
      (node (ref "J4") (pin "5") (pinfunction "2_5") (pintype "passive"))
      (node (ref "J6") (pin "1") (pinfunction "1_1") (pintype "passive"))
      (node (ref "J6") (pin "2") (pinfunction "2_2") (pintype "passive"))
      (node (ref "J6") (pin "3") (pinfunction "2_3") (pintype "passive"))
      (node (ref "J6") (pin "4") (pinfunction "2_4") (pintype "passive"))
      (node (ref "J6") (pin "5") (pinfunction "2_5") (pintype "passive"))
      (node (ref "J7") (pin "2") (pinfunction "2_2") (pintype "passive"))
      (node (ref "J7") (pin "3") (pinfunction "2_3") (pintype "passive"))
      (node (ref "J7") (pin "4") (pinfunction "2_4") (pintype "passive"))
      (node (ref "J7") (pin "5") (pinfunction "2_5") (pintype "passive"))
      (node (ref "J8") (pin "2") (pinfunction "2_2") (pintype "passive"))
      (node (ref "J8") (pin "3") (pinfunction "2_3") (pintype "passive"))
      (node (ref "J8") (pin "4") (pinfunction "2_4") (pintype "passive"))
      (node (ref "J8") (pin "5") (pinfunction "2_5") (pintype "passive"))
      (node (ref "JP1") (pin "1") (pinfunction "1_1") (pintype "passive"))
      (node (ref "JP2") (pin "1") (pinfunction "1_1") (pintype "passive"))
      (node (ref "JP3") (pin "1") (pinfunction "1_1") (pintype "passive"))
      (node (ref "JP4") (pin "1") (pinfunction "1_1") (pintype "passive"))
      (node (ref "JP5") (pin "1") (pinfunction "1_1") (pintype "passive"))
      (node (ref "JP6") (pin "1") (pinfunction "1_1") (pintype "passive"))
      (node (ref "R13") (pin "1") (pinfunction "1_1") (pintype "passive"))
      (node (ref "R14") (pin "1") (pinfunction "1_1") (pintype "passive"))
      (node (ref "R15") (pin "2") (pinfunction "2_2") (pintype "passive"))
      (node (ref "R25") (pin "1") (pinfunction "1_1") (pintype "passive"))
      (node (ref "R27") (pin "1") (pinfunction "1_1") (pintype "passive"))
      (node (ref "R33") (pin "1") (pinfunction "1_1") (pintype "passive"))
      (node (ref "R35") (pin "1") (pinfunction "1_1") (pintype "passive"))
      (node (ref "R9") (pin "1") (pinfunction "1_1") (pintype "passive"))
      (node (ref "U1") (pin "10") (pinfunction "VREFCOM_10") (pintype "output"))
      (node (ref "U1") (pin "2") (pinfunction "DGND_2") (pintype "power_in"))
      (node (ref "U1") (pin "3") (pinfunction "CLK_3") (pintype "input"))
      (node (ref "U4") (pin "1") (pinfunction "GND_1") (pintype "power_in"))
    )
    (net (code "24") (name "IRQ_~{DRDY}") (class "Default")
      (node (ref "ESP32_H_2") (pin "11") (pinfunction "11_11") (pintype "passive"))
    )
    (net (code "25") (name "MC_MISO{slash}~{DRDY}") (class "Default")
      (node (ref "AT1") (pin "6") (pinfunction "OUT4_6") (pintype "bidirectional"))
      (node (ref "ESP32_H_2") (pin "10") (pinfunction "10_10") (pintype "passive"))
    )
    (net (code "26") (name "MC_MOSI") (class "Default")
      (node (ref "AT1") (pin "5") (pinfunction "IN3_5") (pintype "bidirectional"))
      (node (ref "ESP32_H_2") (pin "15") (pinfunction "15_15") (pintype "passive"))
    )
    (net (code "27") (name "MC_RESET") (class "Default")
      (node (ref "AT1") (pin "3") (pinfunction "IN1_3") (pintype "bidirectional"))
      (node (ref "ESP32_H_2") (pin "8") (pinfunction "8_8") (pintype "passive"))
    )
    (net (code "28") (name "MC_SCLK") (class "Default")
      (node (ref "AT1") (pin "4") (pinfunction "IN2_4") (pintype "bidirectional"))
      (node (ref "ESP32_H_2") (pin "9") (pinfunction "9_9") (pintype "passive"))
    )
    (net (code "29") (name "MISO{slash}~{DRDY}") (class "Default")
      (node (ref "AT1") (pin "11") (pinfunction "IN4_11") (pintype "bidirectional"))
      (node (ref "R11") (pin "2") (pinfunction "2_2") (pintype "passive"))
      (node (ref "U1") (pin "26") (pinfunction "DOUT/~{DRDY}_26") (pintype "output"))
    )
    (net (code "30") (name "MOSI") (class "Default")
      (node (ref "AT1") (pin "12") (pinfunction "OUT3_12") (pintype "bidirectional"))
      (node (ref "R10") (pin "2") (pinfunction "2_2") (pintype "passive"))
      (node (ref "U1") (pin "27") (pinfunction "DIN_27") (pintype "input"))
    )
    (net (code "31") (name "Net-(C2-Pad1)") (class "Default")
      (node (ref "C2") (pin "1") (pinfunction "1_1") (pintype "passive"))
      (node (ref "C21") (pin "1") (pinfunction "1_1") (pintype "passive"))
      (node (ref "R16") (pin "2") (pinfunction "2_2") (pintype "passive"))
      (node (ref "R3") (pin "1") (pinfunction "1_1") (pintype "passive"))
    )
    (net (code "32") (name "Net-(C22-Pad1)") (class "Default")
      (node (ref "C22") (pin "1") (pinfunction "1_1") (pintype "passive"))
      (node (ref "C23") (pin "1") (pinfunction "1_1") (pintype "passive"))
      (node (ref "R17") (pin "1") (pinfunction "1_1") (pintype "passive"))
      (node (ref "R18") (pin "2") (pinfunction "2_2") (pintype "passive"))
    )
    (net (code "33") (name "Net-(C24-Pad1)") (class "Default")
      (node (ref "C24") (pin "1") (pinfunction "1_1") (pintype "passive"))
      (node (ref "C25") (pin "1") (pinfunction "1_1") (pintype "passive"))
      (node (ref "R12") (pin "2") (pinfunction "2_2") (pintype "passive"))
      (node (ref "R4") (pin "1") (pinfunction "1_1") (pintype "passive"))
    )
    (net (code "34") (name "Net-(C26-Pad1)") (class "Default")
      (node (ref "C26") (pin "1") (pinfunction "1_1") (pintype "passive"))
      (node (ref "C27") (pin "1") (pinfunction "1_1") (pintype "passive"))
      (node (ref "R19") (pin "1") (pinfunction "1_1") (pintype "passive"))
      (node (ref "R20") (pin "2") (pinfunction "2_2") (pintype "passive"))
    )
    (net (code "35") (name "Net-(C66-Pad1)") (class "Default")
      (node (ref "C66") (pin "1") (pinfunction "1_1") (pintype "passive"))
      (node (ref "C67") (pin "1") (pinfunction "1_1") (pintype "passive"))
      (node (ref "R40") (pin "1") (pinfunction "1_1") (pintype "passive"))
      (node (ref "R43") (pin "2") (pinfunction "2_2") (pintype "passive"))
    )
    (net (code "36") (name "Net-(C68-Pad1)") (class "Default")
      (node (ref "C68") (pin "1") (pinfunction "1_1") (pintype "passive"))
      (node (ref "C69") (pin "1") (pinfunction "1_1") (pintype "passive"))
      (node (ref "R44") (pin "1") (pinfunction "1_1") (pintype "passive"))
      (node (ref "R45") (pin "2") (pinfunction "2_2") (pintype "passive"))
    )
    (net (code "37") (name "Net-(U1-START)") (class "Default")
      (node (ref "C17") (pin "1") (pinfunction "1_1") (pintype "passive"))
      (node (ref "R2") (pin "1") (pinfunction "1_1") (pintype "passive"))
      (node (ref "U1") (pin "23") (pinfunction "START_23") (pintype "input"))
    )
    (net (code "38") (name "Net-(U1-VREFOUT)") (class "Default")
      (node (ref "C8") (pin "2") (pinfunction "2_2") (pintype "passive"))
      (node (ref "U1") (pin "9") (pinfunction "VREFOUT_9") (pintype "output"))
    )
    (net (code "39") (name "Net-(U1-~{CS})") (class "Default")
      (node (ref "R15") (pin "1") (pinfunction "1_1") (pintype "passive"))
      (node (ref "U1") (pin "24") (pinfunction "~{CS}_24") (pintype "input"))
    )
    (net (code "40") (name "Net-(U3-1IN+)") (class "Default")
      (node (ref "R12") (pin "1") (pinfunction "1_1") (pintype "passive"))
      (node (ref "U3") (pin "3") (pinfunction "1IN+_3") (pintype "input"))
    )
    (net (code "41") (name "Net-(U3-2IN+)") (class "Default")
      (node (ref "R20") (pin "1") (pinfunction "1_1") (pintype "passive"))
      (node (ref "U3") (pin "5") (pinfunction "2IN+_5") (pintype "input"))
    )
    (net (code "42") (name "Net-(U3-3IN+)") (class "Default")
      (node (ref "R45") (pin "1") (pinfunction "1_1") (pintype "passive"))
      (node (ref "U3") (pin "10") (pinfunction "3IN+_10") (pintype "input"))
    )
    (net (code "43") (name "Net-(U3-4IN+)") (class "Default")
      (node (ref "R43") (pin "1") (pinfunction "1_1") (pintype "passive"))
      (node (ref "U3") (pin "12") (pinfunction "4IN+_12") (pintype "input"))
    )
    (net (code "44") (name "Net-(U4-EN)") (class "Default")
      (node (ref "R7") (pin "2") (pinfunction "2_2") (pintype "passive"))
      (node (ref "U4") (pin "3") (pinfunction "EN_3") (pintype "input"))
    )
    (net (code "45") (name "Net-(U6-1IN-)") (class "Default")
      (node (ref "R42") (pin "1") (pinfunction "1_1") (pintype "passive"))
      (node (ref "U6") (pin "2") (pinfunction "1IN-_2") (pintype "input"))
    )
    (net (code "46") (name "Net-(U6-2IN+)") (class "Default")
      (node (ref "R18") (pin "1") (pinfunction "1_1") (pintype "passive"))
      (node (ref "U6") (pin "5") (pinfunction "2IN+_5") (pintype "input"))
    )
    (net (code "47") (name "Net-(U6-3IN+)") (class "Default")
      (node (ref "R16") (pin "1") (pinfunction "1_1") (pintype "passive"))
      (node (ref "U6") (pin "10") (pinfunction "3IN+_10") (pintype "input"))
    )
    (net (code "48") (name "Net-(U6-4IN-)") (class "Default")
      (node (ref "R41") (pin "1") (pinfunction "1_1") (pintype "passive"))
      (node (ref "U6") (pin "13") (pinfunction "4IN-_13") (pintype "input"))
    )
    (net (code "49") (name "Net-(U7-1IN-)") (class "Default")
      (node (ref "R39") (pin "1") (pinfunction "1_1") (pintype "passive"))
      (node (ref "U7") (pin "2") (pinfunction "1IN-_2") (pintype "input"))
    )
    (net (code "50") (name "Net-(U7-2IN-)") (class "Default")
      (node (ref "R38") (pin "1") (pinfunction "1_1") (pintype "passive"))
      (node (ref "U7") (pin "6") (pinfunction "2IN-_6") (pintype "input"))
    )
    (net (code "51") (name "Net-(U7-3IN-)") (class "Default")
      (node (ref "R37") (pin "1") (pinfunction "1_1") (pintype "passive"))
      (node (ref "U7") (pin "9") (pinfunction "3IN-_9") (pintype "input"))
    )
    (net (code "52") (name "Net-(U7-4IN-)") (class "Default")
      (node (ref "R36") (pin "1") (pinfunction "1_1") (pintype "passive"))
      (node (ref "U7") (pin "13") (pinfunction "4IN-_13") (pintype "input"))
    )
    (net (code "53") (name "OUT1") (class "Default")
      (node (ref "C69") (pin "2") (pinfunction "2_2") (pintype "passive"))
      (node (ref "R23") (pin "2") (pinfunction "2_2") (pintype "passive"))
      (node (ref "U3") (pin "8") (pinfunction "3OUT_8") (pintype "output"))
      (node (ref "U3") (pin "9") (pinfunction "3IN-_9") (pintype "input"))
    )
    (net (code "54") (name "OUT1_WT") (class "Default")
      (node (ref "R39") (pin "2") (pinfunction "2_2") (pintype "passive"))
      (node (ref "R44") (pin "2") (pinfunction "2_2") (pintype "passive"))
      (node (ref "U7") (pin "1") (pinfunction "1OUT_1") (pintype "output"))
    )
    (net (code "55") (name "OUT2") (class "Default")
      (node (ref "C67") (pin "2") (pinfunction "2_2") (pintype "passive"))
      (node (ref "R1") (pin "2") (pinfunction "2_2") (pintype "passive"))
      (node (ref "U3") (pin "13") (pinfunction "4IN-_13") (pintype "input"))
      (node (ref "U3") (pin "14") (pinfunction "4OUT_14") (pintype "output"))
    )
    (net (code "56") (name "OUT2_WT") (class "Default")
      (node (ref "R38") (pin "2") (pinfunction "2_2") (pintype "passive"))
      (node (ref "R40") (pin "2") (pinfunction "2_2") (pintype "passive"))
      (node (ref "U7") (pin "7") (pinfunction "2OUT_7") (pintype "output"))
    )
    (net (code "57") (name "OUT3") (class "Default")
      (node (ref "C25") (pin "2") (pinfunction "2_2") (pintype "passive"))
      (node (ref "R24") (pin "2") (pinfunction "2_2") (pintype "passive"))
      (node (ref "U3") (pin "1") (pinfunction "1OUT_1") (pintype "output"))
      (node (ref "U3") (pin "2") (pinfunction "1IN-_2") (pintype "input"))
    )
    (net (code "58") (name "OUT3_WT") (class "Default")
      (node (ref "R37") (pin "2") (pinfunction "2_2") (pintype "passive"))
      (node (ref "R4") (pin "2") (pinfunction "2_2") (pintype "passive"))
      (node (ref "U7") (pin "8") (pinfunction "3OUT_8") (pintype "output"))
    )
    (net (code "59") (name "OUT4") (class "Default")
      (node (ref "C27") (pin "2") (pinfunction "2_2") (pintype "passive"))
      (node (ref "R26") (pin "2") (pinfunction "2_2") (pintype "passive"))
      (node (ref "U3") (pin "6") (pinfunction "2IN-_6") (pintype "input"))
      (node (ref "U3") (pin "7") (pinfunction "2OUT_7") (pintype "output"))
    )
    (net (code "60") (name "OUT4_WT") (class "Default")
      (node (ref "R19") (pin "2") (pinfunction "2_2") (pintype "passive"))
      (node (ref "R36") (pin "2") (pinfunction "2_2") (pintype "passive"))
      (node (ref "U7") (pin "14") (pinfunction "4OUT_14") (pintype "output"))
    )
    (net (code "61") (name "OUT5") (class "Default")
      (node (ref "C23") (pin "2") (pinfunction "2_2") (pintype "passive"))
      (node (ref "R32") (pin "2") (pinfunction "2_2") (pintype "passive"))
      (node (ref "U6") (pin "6") (pinfunction "2IN-_6") (pintype "input"))
      (node (ref "U6") (pin "7") (pinfunction "2OUT_7") (pintype "output"))
    )
    (net (code "62") (name "OUT5_WT") (class "Default")
      (node (ref "R17") (pin "2") (pinfunction "2_2") (pintype "passive"))
      (node (ref "R42") (pin "2") (pinfunction "2_2") (pintype "passive"))
      (node (ref "U6") (pin "1") (pinfunction "1OUT_1") (pintype "output"))
    )
    (net (code "63") (name "OUT6") (class "Default")
      (node (ref "C21") (pin "2") (pinfunction "2_2") (pintype "passive"))
      (node (ref "R34") (pin "2") (pinfunction "2_2") (pintype "passive"))
      (node (ref "U6") (pin "8") (pinfunction "3OUT_8") (pintype "output"))
      (node (ref "U6") (pin "9") (pinfunction "3IN-_9") (pintype "input"))
    )
    (net (code "64") (name "OUT6_WT") (class "Default")
      (node (ref "R3") (pin "2") (pinfunction "2_2") (pintype "passive"))
      (node (ref "R41") (pin "2") (pinfunction "2_2") (pintype "passive"))
      (node (ref "U6") (pin "14") (pinfunction "4OUT_14") (pintype "output"))
    )
    (net (code "65") (name "RESET_ADC") (class "Default")
      (node (ref "AT1") (pin "14") (pinfunction "OUT1_14") (pintype "bidirectional"))
      (node (ref "R5") (pin "2") (pinfunction "2_2") (pintype "passive"))
      (node (ref "U1") (pin "4") (pinfunction "~{RESET}_4") (pintype "input"))
    )
    (net (code "66") (name "RX2") (class "Default")
      (node (ref "ESP32_H_2") (pin "6") (pinfunction "6_6") (pintype "passive"))
      (node (ref "IC2") (pin "1") (pinfunction "RO_1") (pintype "bidirectional"))
    )
    (net (code "67") (name "TX2") (class "Default")
      (node (ref "ESP32_H_2") (pin "7") (pinfunction "7_7") (pintype "passive"))
      (node (ref "IC2") (pin "4") (pinfunction "DI_4") (pintype "bidirectional"))
    )
    (net (code "68") (name "WT5") (class "Default")
      (node (ref "U6") (pin "3") (pinfunction "1IN+_3") (pintype "input"))
    )
    (net (code "69") (name "WT6") (class "Default")
      (node (ref "U6") (pin "12") (pinfunction "4IN+_12") (pintype "input"))
    )
    (net (code "70") (name "unconnected-(AM1G-1205D-NZ-CNTL-Pad3)") (class "Default")
      (node (ref "AM1G-1205D-NZ") (pin "3") (pinfunction "CNTL_3") (pintype "bidirectional"))
    )
    (net (code "71") (name "unconnected-(AM1G-1205D-NZ-NC-Pad5)") (class "Default")
      (node (ref "AM1G-1205D-NZ") (pin "5") (pinfunction "NC_5") (pintype "bidirectional"))
    )
    (net (code "72") (name "unconnected-(AT1-NC_1-Pad7)") (class "Default")
      (node (ref "AT1") (pin "7") (pinfunction "NC_1_7") (pintype "bidirectional"))
    )
    (net (code "73") (name "unconnected-(AT1-NC_2-Pad10)") (class "Default")
      (node (ref "AT1") (pin "10") (pinfunction "NC_2_10") (pintype "bidirectional"))
    )
    (net (code "74") (name "unconnected-(ESP32_H_1-Pad2)") (class "Default")
      (node (ref "ESP32_H_1") (pin "2") (pinfunction "2_2") (pintype "passive"))
    )
    (net (code "75") (name "unconnected-(ESP32_H_1-Pad3)") (class "Default")
      (node (ref "ESP32_H_1") (pin "3") (pinfunction "3_3") (pintype "passive"))
    )
    (net (code "76") (name "unconnected-(ESP32_H_1-Pad5)") (class "Default")
      (node (ref "ESP32_H_1") (pin "5") (pinfunction "5_5") (pintype "passive"))
    )
    (net (code "77") (name "unconnected-(ESP32_H_1-Pad6)") (class "Default")
      (node (ref "ESP32_H_1") (pin "6") (pinfunction "6_6") (pintype "passive"))
    )
    (net (code "78") (name "unconnected-(ESP32_H_1-Pad7)") (class "Default")
      (node (ref "ESP32_H_1") (pin "7") (pinfunction "7_7") (pintype "passive"))
    )
    (net (code "79") (name "unconnected-(ESP32_H_1-Pad8)") (class "Default")
      (node (ref "ESP32_H_1") (pin "8") (pinfunction "8_8") (pintype "passive"))
    )
    (net (code "80") (name "unconnected-(ESP32_H_1-Pad9)") (class "Default")
      (node (ref "ESP32_H_1") (pin "9") (pinfunction "9_9") (pintype "passive"))
    )
    (net (code "81") (name "unconnected-(ESP32_H_1-Pad10)") (class "Default")
      (node (ref "ESP32_H_1") (pin "10") (pinfunction "10_10") (pintype "passive"))
    )
    (net (code "82") (name "unconnected-(ESP32_H_1-Pad11)") (class "Default")
      (node (ref "ESP32_H_1") (pin "11") (pinfunction "11_11") (pintype "passive"))
    )
    (net (code "83") (name "unconnected-(ESP32_H_1-Pad12)") (class "Default")
      (node (ref "ESP32_H_1") (pin "12") (pinfunction "12_12") (pintype "passive"))
    )
    (net (code "84") (name "unconnected-(ESP32_H_1-Pad13)") (class "Default")
      (node (ref "ESP32_H_1") (pin "13") (pinfunction "13_13") (pintype "passive"))
    )
    (net (code "85") (name "unconnected-(ESP32_H_1-Pad14)") (class "Default")
      (node (ref "ESP32_H_1") (pin "14") (pinfunction "14_14") (pintype "passive"))
    )
    (net (code "86") (name "unconnected-(ESP32_H_2-Pad2)") (class "Default")
      (node (ref "ESP32_H_2") (pin "2") (pinfunction "2_2") (pintype "passive"))
    )
    (net (code "87") (name "unconnected-(ESP32_H_2-Pad3)") (class "Default")
      (node (ref "ESP32_H_2") (pin "3") (pinfunction "3_3") (pintype "passive"))
    )
    (net (code "88") (name "unconnected-(ESP32_H_2-Pad4)") (class "Default")
      (node (ref "ESP32_H_2") (pin "4") (pinfunction "4_4") (pintype "passive"))
    )
    (net (code "89") (name "unconnected-(ESP32_H_2-Pad12)") (class "Default")
      (node (ref "ESP32_H_2") (pin "12") (pinfunction "12_12") (pintype "passive"))
    )
    (net (code "90") (name "unconnected-(ESP32_H_2-Pad13)") (class "Default")
      (node (ref "ESP32_H_2") (pin "13") (pinfunction "13_13") (pintype "passive"))
    )
    (net (code "91") (name "unconnected-(ESP32_H_2-Pad14)") (class "Default")
      (node (ref "ESP32_H_2") (pin "14") (pinfunction "14_14") (pintype "passive"))
    )
    (net (code "92") (name "unconnected-(IC1-EN-Pad3)") (class "Default")
      (node (ref "IC1") (pin "3") (pinfunction "EN_3") (pintype "bidirectional"))
    )
    (net (code "93") (name "unconnected-(IC1-NC-Pad4)") (class "Default")
      (node (ref "IC1") (pin "4") (pinfunction "NC_4") (pintype "no_connect"))
    )
    (net (code "94") (name "unconnected-(J1-Pad1)") (class "Default")
      (node (ref "J1") (pin "1") (pinfunction "1_1") (pintype "passive"))
    )
    (net (code "95") (name "unconnected-(J2-Pad1)") (class "Default")
      (node (ref "J2") (pin "1") (pinfunction "1_1") (pintype "passive"))
    )
    (net (code "96") (name "unconnected-(J3-Pad1)") (class "Default")
      (node (ref "J3") (pin "1") (pinfunction "1_1") (pintype "passive"))
    )
    (net (code "97") (name "unconnected-(J4-Pad1)") (class "Default")
      (node (ref "J4") (pin "1") (pinfunction "1_1") (pintype "passive"))
    )
    (net (code "98") (name "unconnected-(J7-Pad1)") (class "Default")
      (node (ref "J7") (pin "1") (pinfunction "1_1") (pintype "passive"))
    )
    (net (code "99") (name "unconnected-(J8-Pad1)") (class "Default")
      (node (ref "J8") (pin "1") (pinfunction "1_1") (pintype "passive"))
    )
    (net (code "100") (name "unconnected-(R5-Pad1)") (class "Default")
      (node (ref "R5") (pin "1") (pinfunction "1_1") (pintype "passive"))
    )
    (net (code "101") (name "unconnected-(R6-Pad1)") (class "Default")
      (node (ref "R6") (pin "1") (pinfunction "1_1") (pintype "passive"))
    )
    (net (code "102") (name "unconnected-(R10-Pad1)") (class "Default")
      (node (ref "R10") (pin "1") (pinfunction "1_1") (pintype "passive"))
    )
    (net (code "103") (name "unconnected-(R11-Pad1)") (class "Default")
      (node (ref "R11") (pin "1") (pinfunction "1_1") (pintype "passive"))
    )
    (net (code "104") (name "unconnected-(U1-IEXC1-Pad20)") (class "Default")
      (node (ref "U1") (pin "20") (pinfunction "IEXC1_20") (pintype "output"))
    )
    (net (code "105") (name "unconnected-(U1-IEXC2-Pad19)") (class "Default")
      (node (ref "U1") (pin "19") (pinfunction "IEXC2_19") (pintype "output"))
    )
    (net (code "106") (name "unconnected-(U1-REFN0{slash}GPIO1-Pad6)") (class "Default")
      (node (ref "U1") (pin "6") (pinfunction "REFN0/GPIO1_6") (pintype "bidirectional"))
    )
    (net (code "107") (name "unconnected-(U1-REFN1-Pad8)") (class "Default")
      (node (ref "U1") (pin "8") (pinfunction "REFN1_8") (pintype "input"))
    )
    (net (code "108") (name "unconnected-(U1-REFP0{slash}GPIO0-Pad5)") (class "Default")
      (node (ref "U1") (pin "5") (pinfunction "REFP0/GPIO0_5") (pintype "bidirectional"))
    )
    (net (code "109") (name "unconnected-(U1-REFP1-Pad7)") (class "Default")
      (node (ref "U1") (pin "7") (pinfunction "REFP1_7") (pintype "input"))
    )
    (net (code "110") (name "unconnected-(U1-~{DRDY}-Pad25)") (class "Default")
      (node (ref "U1") (pin "25") (pinfunction "~{DRDY}_25") (pintype "input"))
    )
    (net (code "111") (name "unconnected-(U7-1IN+-Pad3)") (class "Default")
      (node (ref "U7") (pin "3") (pinfunction "1IN+_3") (pintype "input"))
    )
    (net (code "112") (name "unconnected-(U7-2IN+-Pad5)") (class "Default")
      (node (ref "U7") (pin "5") (pinfunction "2IN+_5") (pintype "input"))
    )
    (net (code "113") (name "unconnected-(U7-3IN+-Pad10)") (class "Default")
      (node (ref "U7") (pin "10") (pinfunction "3IN+_10") (pintype "input"))
    )
    (net (code "114") (name "unconnected-(U7-4IN+-Pad12)") (class "Default")
      (node (ref "U7") (pin "12") (pinfunction "4IN+_12") (pintype "input"))
    )
    (net (code "115") (name "unconnected-(X2-Pad5)") (class "Default")
      (node (ref "X2") (pin "5") (pinfunction "5_5") (pintype "passive"))
    )
    (net (code "116") (name "unconnected-(X2-Pad6)") (class "Default")
      (node (ref "X2") (pin "6") (pinfunction "6_6") (pintype "passive"))
    )
    (net (code "117") (name "unconnected-(X2-Pad7)") (class "Default")
      (node (ref "X2") (pin "7") (pinfunction "7_7") (pintype "passive"))
    )
    (net (code "118") (name "unconnected-(X2-S1-PadS@1)") (class "Default")
      (node (ref "X2") (pin "S@1") (pinfunction "S1_S@1") (pintype "passive"))
    )
    (net (code "119") (name "unconnected-(X2-S2-PadS@2)") (class "Default")
      (node (ref "X2") (pin "S@2") (pinfunction "S2_S@2") (pintype "passive"))
    )
  )
)
